# read_out.net
KiCad netlist of a schematic drawn in Altium Designer
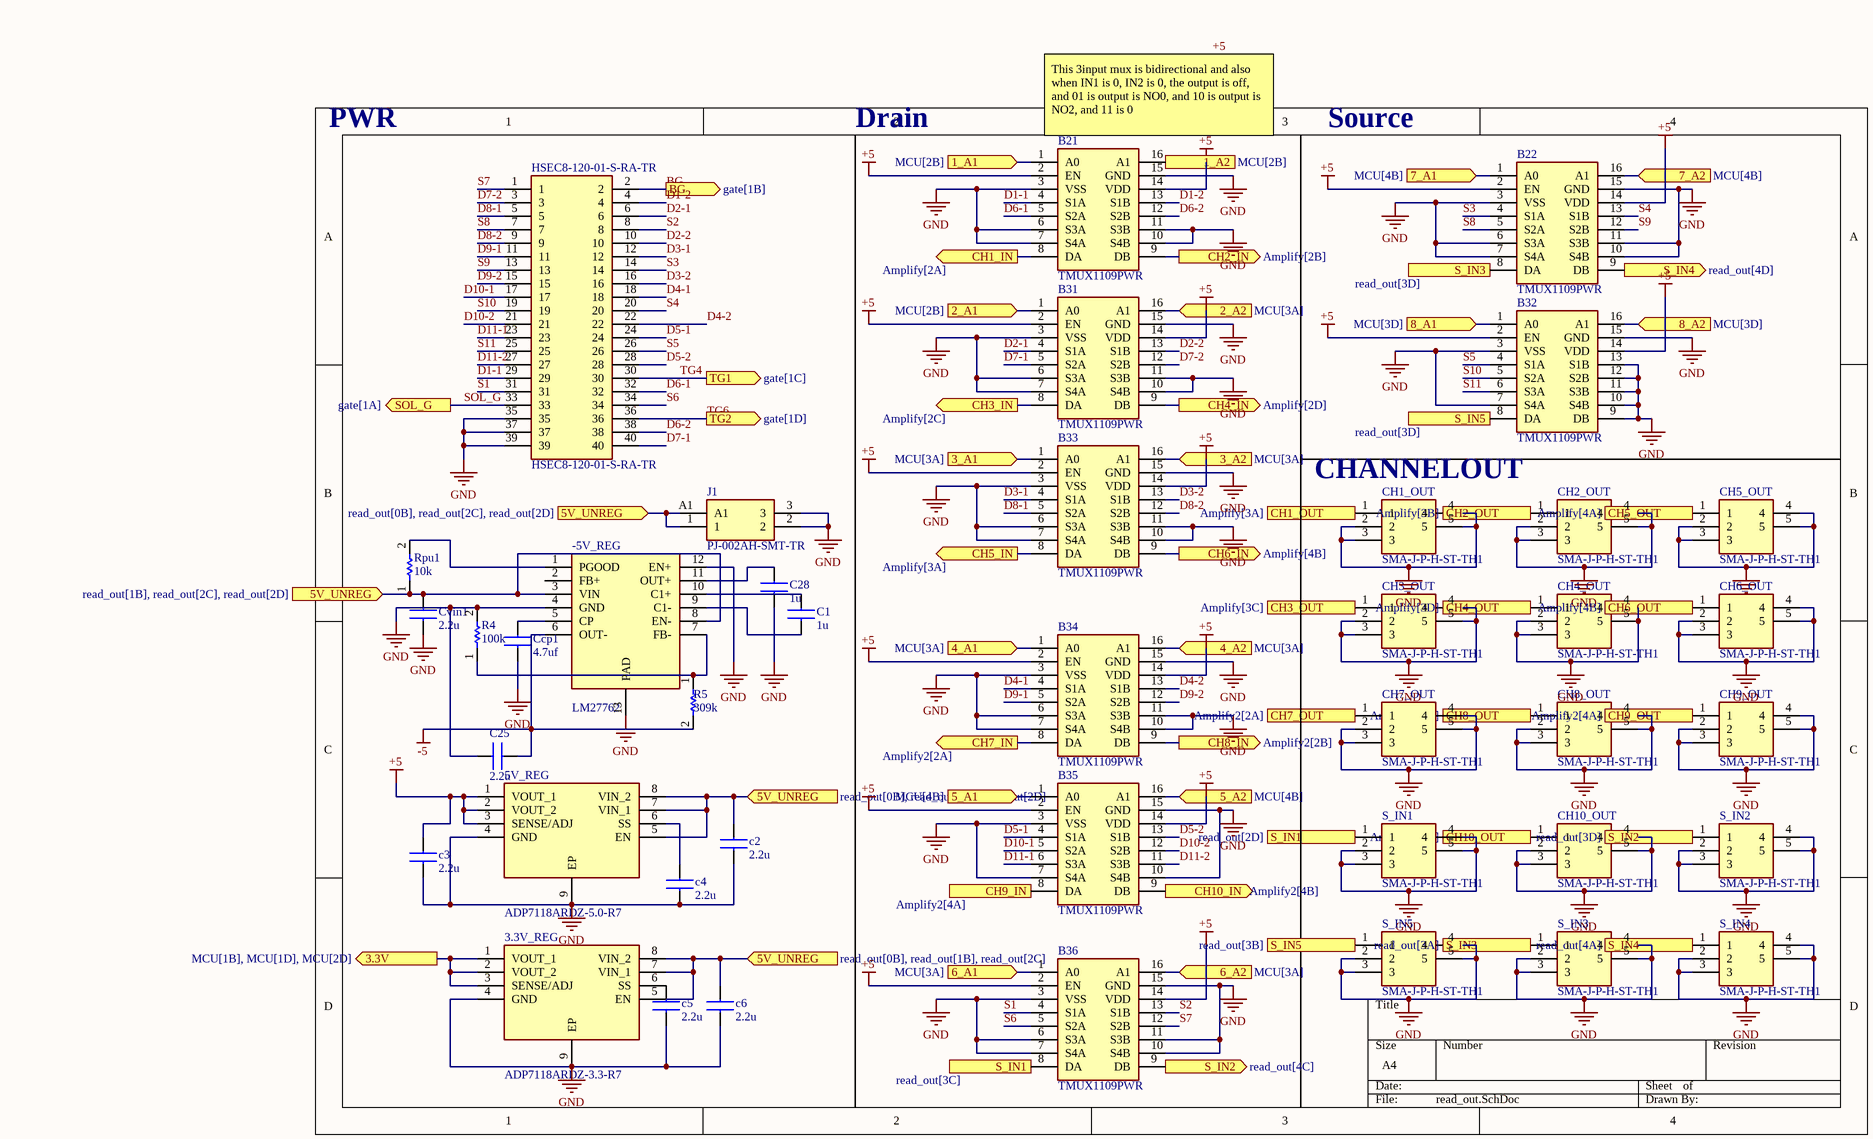
[diagram p0: read_out.SchDoc]

(export (version "E")
  (design (tool "Eeschema 10.0.6"))
  (components
    (comp (ref "-5V_REG")
      (value "LM27762")
      (footprint "LM27762")
      (libsource (lib "Schlib1") (part "LM27762"))
    )
    (comp (ref "3.3V_REG")
      (value "ADP7118ARDZ-3.3-R7")
      (footprint "ADP7118ARDZ-5.0-R7")
      (libsource (lib "Schlib1") (part "ADP7118ARDZ-5.0-R7"))
    )
    (comp (ref "5V_REG")
      (value "ADP7118ARDZ-5.0-R7")
      (footprint "ADP7118ARDZ-5.0-R7")
      (libsource (lib "Schlib1") (part "ADP7118ARDZ-5.0-R7"))
    )
    (comp (ref "B21")
      (value "TMUX1109PWR")
      (footprint "TMUX1109PWR")
      (libsource (lib "Schlib1") (part "TMUX1109PWR"))
    )
    (comp (ref "B22")
      (value "TMUX1109PWR")
      (footprint "TMUX1109PWR")
      (libsource (lib "Schlib1") (part "TMUX1109PWR"))
    )
    (comp (ref "B31")
      (value "TMUX1109PWR")
      (footprint "TMUX1109PWR")
      (libsource (lib "Schlib1") (part "TMUX1109PWR"))
    )
    (comp (ref "B32")
      (value "TMUX1109PWR")
      (footprint "TMUX1109PWR")
      (libsource (lib "Schlib1") (part "TMUX1109PWR"))
    )
    (comp (ref "B33")
      (value "TMUX1109PWR")
      (footprint "TMUX1109PWR")
      (libsource (lib "Schlib1") (part "TMUX1109PWR"))
    )
    (comp (ref "B34")
      (value "TMUX1109PWR")
      (footprint "TMUX1109PWR")
      (libsource (lib "Schlib1") (part "TMUX1109PWR"))
    )
    (comp (ref "B35")
      (value "TMUX1109PWR")
      (footprint "TMUX1109PWR")
      (libsource (lib "Schlib1") (part "TMUX1109PWR"))
    )
    (comp (ref "B36")
      (value "TMUX1109PWR")
      (footprint "TMUX1109PWR")
      (libsource (lib "Schlib1") (part "TMUX1109PWR"))
    )
    (comp (ref "C1")
      (value "1u")
      (footprint "0805X7R106KT1AT")
      (libsource (lib "Schlib1") (part "capacitor"))
    )
    (comp (ref "c2")
      (value "2.2u")
      (footprint "0805X7R106KT1AT")
      (libsource (lib "Schlib1") (part "capacitor"))
    )
    (comp (ref "c3")
      (value "2.2u")
      (footprint "0805X7R106KT1AT")
      (libsource (lib "Schlib1") (part "capacitor"))
    )
    (comp (ref "c4")
      (value "2.2u")
      (footprint "0805X7R106KT1AT")
      (libsource (lib "Schlib1") (part "capacitor"))
    )
    (comp (ref "c5")
      (value "2.2u")
      (footprint "0805X7R106KT1AT")
      (libsource (lib "Schlib1") (part "capacitor"))
    )
    (comp (ref "c6")
      (value "2.2u")
      (footprint "0805X7R106KT1AT")
      (libsource (lib "Schlib1") (part "capacitor"))
    )
    (comp (ref "C25")
      (value "2.2u")
      (footprint "0805X7R106KT1AT")
      (libsource (lib "Schlib1") (part "capacitor"))
    )
    (comp (ref "C28")
      (value "1u")
      (footprint "0805X7R106KT1AT")
      (libsource (lib "Schlib1") (part "capacitor"))
    )
    (comp (ref "Ccp1")
      (value "4.7uf")
      (footprint "0805X7R106KT1AT")
      (libsource (lib "Schlib1") (part "capacitor"))
    )
    (comp (ref "CH1_OUT")
      (value "SMA-J-P-H-ST-TH1")
      (footprint "SMAJPHSTTH1")
      (description "SAMTEC - SMA-J-P-H-ST-TH1 - RF COAXIAL, SMA JACK, 50 OHM, PCB")
      (fields (field (name "MOUSER PART NUMBER") "200-SMAJPHSTTH1"))
      (libsource (lib "Schlib1") (part "SMA-J-P-H-ST-TH1"))
    )
    (comp (ref "CH2_OUT")
      (value "SMA-J-P-H-ST-TH1")
      (footprint "SMAJPHSTTH1")
      (description "SAMTEC - SMA-J-P-H-ST-TH1 - RF COAXIAL, SMA JACK, 50 OHM, PCB")
      (fields (field (name "MOUSER PART NUMBER") "200-SMAJPHSTTH1"))
      (libsource (lib "Schlib1") (part "SMA-J-P-H-ST-TH1"))
    )
    (comp (ref "CH3_OUT")
      (value "SMA-J-P-H-ST-TH1")
      (footprint "SMAJPHSTTH1")
      (description "SAMTEC - SMA-J-P-H-ST-TH1 - RF COAXIAL, SMA JACK, 50 OHM, PCB")
      (fields (field (name "MOUSER PART NUMBER") "200-SMAJPHSTTH1"))
      (libsource (lib "Schlib1") (part "SMA-J-P-H-ST-TH1"))
    )
    (comp (ref "CH4_OUT")
      (value "SMA-J-P-H-ST-TH1")
      (footprint "SMAJPHSTTH1")
      (description "SAMTEC - SMA-J-P-H-ST-TH1 - RF COAXIAL, SMA JACK, 50 OHM, PCB")
      (fields (field (name "MOUSER PART NUMBER") "200-SMAJPHSTTH1"))
      (libsource (lib "Schlib1") (part "SMA-J-P-H-ST-TH1"))
    )
    (comp (ref "CH5_OUT")
      (value "SMA-J-P-H-ST-TH1")
      (footprint "SMAJPHSTTH1")
      (description "SAMTEC - SMA-J-P-H-ST-TH1 - RF COAXIAL, SMA JACK, 50 OHM, PCB")
      (fields (field (name "MOUSER PART NUMBER") "200-SMAJPHSTTH1"))
      (libsource (lib "Schlib1") (part "SMA-J-P-H-ST-TH1"))
    )
    (comp (ref "CH6_OUT")
      (value "SMA-J-P-H-ST-TH1")
      (footprint "SMAJPHSTTH1")
      (description "SAMTEC - SMA-J-P-H-ST-TH1 - RF COAXIAL, SMA JACK, 50 OHM, PCB")
      (fields (field (name "MOUSER PART NUMBER") "200-SMAJPHSTTH1"))
      (libsource (lib "Schlib1") (part "SMA-J-P-H-ST-TH1"))
    )
    (comp (ref "CH7_OUT")
      (value "SMA-J-P-H-ST-TH1")
      (footprint "SMAJPHSTTH1")
      (description "SAMTEC - SMA-J-P-H-ST-TH1 - RF COAXIAL, SMA JACK, 50 OHM, PCB")
      (fields (field (name "MOUSER PART NUMBER") "200-SMAJPHSTTH1"))
      (libsource (lib "Schlib1") (part "SMA-J-P-H-ST-TH1"))
    )
    (comp (ref "CH8_OUT")
      (value "SMA-J-P-H-ST-TH1")
      (footprint "SMAJPHSTTH1")
      (description "SAMTEC - SMA-J-P-H-ST-TH1 - RF COAXIAL, SMA JACK, 50 OHM, PCB")
      (fields (field (name "MOUSER PART NUMBER") "200-SMAJPHSTTH1"))
      (libsource (lib "Schlib1") (part "SMA-J-P-H-ST-TH1"))
    )
    (comp (ref "CH9_OUT")
      (value "SMA-J-P-H-ST-TH1")
      (footprint "SMAJPHSTTH1")
      (description "SAMTEC - SMA-J-P-H-ST-TH1 - RF COAXIAL, SMA JACK, 50 OHM, PCB")
      (fields (field (name "MOUSER PART NUMBER") "200-SMAJPHSTTH1"))
      (libsource (lib "Schlib1") (part "SMA-J-P-H-ST-TH1"))
    )
    (comp (ref "CH10_OUT")
      (value "SMA-J-P-H-ST-TH1")
      (footprint "SMAJPHSTTH1")
      (description "SAMTEC - SMA-J-P-H-ST-TH1 - RF COAXIAL, SMA JACK, 50 OHM, PCB")
      (fields (field (name "MOUSER PART NUMBER") "200-SMAJPHSTTH1"))
      (libsource (lib "Schlib1") (part "SMA-J-P-H-ST-TH1"))
    )
    (comp (ref "Cvin1")
      (value "2.2u")
      (footprint "0805X7R106KT1AT")
      (libsource (lib "Schlib1") (part "0805X7R106KT1AT"))
    )
    (comp (ref "HSEC8-120-01-S-RA-TR")
      (value "HSEC8-120-01-S-RA-TR")
      (footprint "SAMTEC_HSEC8-120-01-L-RA")
      (libsource (lib "Schlib1") (part "HSEC8-120-01-S-RA-TR"))
    )
    (comp (ref "J1")
      (value "PJ-002AH-SMT-TR")
      (footprint "PWRPJ")
      (libsource (lib "Schlib1") (part "Powerinput"))
    )
    (comp (ref "R4")
      (value "100k")
      (footprint "CR0805-FX-1543ELF")
      (libsource (lib "Schlib1") (part "resistor"))
    )
    (comp (ref "R5")
      (value "309k")
      (footprint "CR0805-FX-1543ELF")
      (libsource (lib "Schlib1") (part "resistor"))
    )
    (comp (ref "Rpu1")
      (value "10k")
      (footprint "CR0805-FX-1543ELF")
      (libsource (lib "Schlib1") (part "resistor"))
    )
    (comp (ref "S_IN1")
      (value "SMA-J-P-H-ST-TH1")
      (footprint "SMAJPHSTTH1")
      (description "SAMTEC - SMA-J-P-H-ST-TH1 - RF COAXIAL, SMA JACK, 50 OHM, PCB")
      (fields (field (name "MOUSER PART NUMBER") "200-SMAJPHSTTH1"))
      (libsource (lib "Schlib1") (part "SMA-J-P-H-ST-TH1"))
    )
    (comp (ref "S_IN2")
      (value "SMA-J-P-H-ST-TH1")
      (footprint "SMAJPHSTTH1")
      (description "SAMTEC - SMA-J-P-H-ST-TH1 - RF COAXIAL, SMA JACK, 50 OHM, PCB")
      (fields (field (name "MOUSER PART NUMBER") "200-SMAJPHSTTH1"))
      (libsource (lib "Schlib1") (part "SMA-J-P-H-ST-TH1"))
    )
    (comp (ref "S_IN3")
      (value "SMA-J-P-H-ST-TH1")
      (footprint "SMAJPHSTTH1")
      (description "SAMTEC - SMA-J-P-H-ST-TH1 - RF COAXIAL, SMA JACK, 50 OHM, PCB")
      (fields (field (name "MOUSER PART NUMBER") "200-SMAJPHSTTH1"))
      (libsource (lib "Schlib1") (part "SMA-J-P-H-ST-TH1"))
    )
    (comp (ref "S_IN4")
      (value "SMA-J-P-H-ST-TH1")
      (footprint "SMAJPHSTTH1")
      (description "SAMTEC - SMA-J-P-H-ST-TH1 - RF COAXIAL, SMA JACK, 50 OHM, PCB")
      (fields (field (name "MOUSER PART NUMBER") "200-SMAJPHSTTH1"))
      (libsource (lib "Schlib1") (part "SMA-J-P-H-ST-TH1"))
    )
    (comp (ref "S_IN5")
      (value "SMA-J-P-H-ST-TH1")
      (footprint "SMAJPHSTTH1")
      (description "SAMTEC - SMA-J-P-H-ST-TH1 - RF COAXIAL, SMA JACK, 50 OHM, PCB")
      (fields (field (name "MOUSER PART NUMBER") "200-SMAJPHSTTH1"))
      (libsource (lib "Schlib1") (part "SMA-J-P-H-ST-TH1"))
    )
  )
  (nets
    (net (code "1") (name "+5") (class "Default")
      (node (ref "5V_REG") (pin "1") (pinfunction "VOUT_1_1") (pintype "passive"))
      (node (ref "5V_REG") (pin "2") (pinfunction "VOUT_2_2") (pintype "passive"))
      (node (ref "5V_REG") (pin "3") (pinfunction "SENSE/ADJ_3") (pintype "passive"))
      (node (ref "B21") (pin "14") (pinfunction "VDD_14") (pintype "passive"))
      (node (ref "B21") (pin "2") (pinfunction "EN_2") (pintype "passive"))
      (node (ref "B22") (pin "14") (pinfunction "VDD_14") (pintype "passive"))
      (node (ref "B22") (pin "2") (pinfunction "EN_2") (pintype "passive"))
      (node (ref "B31") (pin "14") (pinfunction "VDD_14") (pintype "passive"))
      (node (ref "B31") (pin "2") (pinfunction "EN_2") (pintype "passive"))
      (node (ref "B32") (pin "14") (pinfunction "VDD_14") (pintype "passive"))
      (node (ref "B32") (pin "2") (pinfunction "EN_2") (pintype "passive"))
      (node (ref "B33") (pin "14") (pinfunction "VDD_14") (pintype "passive"))
      (node (ref "B33") (pin "2") (pinfunction "EN_2") (pintype "passive"))
      (node (ref "B34") (pin "14") (pinfunction "VDD_14") (pintype "passive"))
      (node (ref "B34") (pin "2") (pinfunction "EN_2") (pintype "passive"))
      (node (ref "B35") (pin "14") (pinfunction "VDD_14") (pintype "passive"))
      (node (ref "B35") (pin "2") (pinfunction "EN_2") (pintype "passive"))
      (node (ref "B36") (pin "14") (pinfunction "VDD_14") (pintype "passive"))
      (node (ref "B36") (pin "2") (pinfunction "EN_2") (pintype "passive"))
      (node (ref "c3") (pin "2") (pinfunction "2_2") (pintype "passive"))
    )
    (net (code "2") (name "-5") (class "Default")
      (node (ref "-5V_REG") (pin "6") (pinfunction "OUT-_6") (pintype "power_in"))
      (node (ref "C25") (pin "1") (pinfunction "1_1") (pintype "passive"))
      (node (ref "R5") (pin "2") (pinfunction "2_2") (pintype "passive"))
    )
    (net (code "3") (name "/1_A1") (class "Default")
      (node (ref "B21") (pin "1") (pinfunction "A0_1") (pintype "passive"))
    )
    (net (code "4") (name "/1_A2") (class "Default")
      (node (ref "B21") (pin "16") (pinfunction "A1_16") (pintype "passive"))
    )
    (net (code "5") (name "/2_A1") (class "Default")
      (node (ref "B31") (pin "1") (pinfunction "A0_1") (pintype "passive"))
    )
    (net (code "6") (name "/2_A2") (class "Default")
      (node (ref "B31") (pin "16") (pinfunction "A1_16") (pintype "passive"))
    )
    (net (code "7") (name "/3.3V") (class "Default")
      (node (ref "3.3V_REG") (pin "1") (pinfunction "VOUT_1_1") (pintype "passive"))
      (node (ref "3.3V_REG") (pin "2") (pinfunction "VOUT_2_2") (pintype "passive"))
      (node (ref "3.3V_REG") (pin "3") (pinfunction "SENSE/ADJ_3") (pintype "passive"))
    )
    (net (code "8") (name "/3_A1") (class "Default")
      (node (ref "B33") (pin "1") (pinfunction "A0_1") (pintype "passive"))
    )
    (net (code "9") (name "/3_A2") (class "Default")
      (node (ref "B33") (pin "16") (pinfunction "A1_16") (pintype "passive"))
    )
    (net (code "10") (name "/4_A1") (class "Default")
      (node (ref "B34") (pin "1") (pinfunction "A0_1") (pintype "passive"))
    )
    (net (code "11") (name "/4_A2") (class "Default")
      (node (ref "B34") (pin "16") (pinfunction "A1_16") (pintype "passive"))
    )
    (net (code "12") (name "/5V_UNREG") (class "Default")
      (node (ref "-5V_REG") (pin "3") (pinfunction "VIN_3") (pintype "power_in"))
      (node (ref "-5V_REG") (pin "8") (pinfunction "EN-_8") (pintype "passive"))
      (node (ref "3.3V_REG") (pin "5") (pinfunction "EN_5") (pintype "passive"))
      (node (ref "3.3V_REG") (pin "7") (pinfunction "VIN_1_7") (pintype "passive"))
      (node (ref "3.3V_REG") (pin "8") (pinfunction "VIN_2_8") (pintype "passive"))
      (node (ref "5V_REG") (pin "5") (pinfunction "EN_5") (pintype "passive"))
      (node (ref "5V_REG") (pin "7") (pinfunction "VIN_1_7") (pintype "passive"))
      (node (ref "5V_REG") (pin "8") (pinfunction "VIN_2_8") (pintype "passive"))
      (node (ref "Cvin1") (pin "2") (pinfunction "2_2") (pintype "passive"))
      (node (ref "J1") (pin "1") (pinfunction "1_1") (pintype "passive"))
      (node (ref "J1") (pin "A1") (pinfunction "A1_A1") (pintype "passive"))
      (node (ref "Rpu1") (pin "1") (pinfunction "1_1") (pintype "passive"))
      (node (ref "c2") (pin "2") (pinfunction "2_2") (pintype "passive"))
      (node (ref "c6") (pin "2") (pinfunction "2_2") (pintype "passive"))
    )
    (net (code "13") (name "/5_A1") (class "Default")
      (node (ref "B35") (pin "1") (pinfunction "A0_1") (pintype "passive"))
    )
    (net (code "14") (name "/5_A2") (class "Default")
      (node (ref "B35") (pin "16") (pinfunction "A1_16") (pintype "passive"))
    )
    (net (code "15") (name "/6_A1") (class "Default")
      (node (ref "B36") (pin "1") (pinfunction "A0_1") (pintype "passive"))
    )
    (net (code "16") (name "/6_A2") (class "Default")
      (node (ref "B36") (pin "16") (pinfunction "A1_16") (pintype "passive"))
    )
    (net (code "17") (name "/7_A1") (class "Default")
      (node (ref "B22") (pin "1") (pinfunction "A0_1") (pintype "passive"))
    )
    (net (code "18") (name "/7_A2") (class "Default")
      (node (ref "B22") (pin "16") (pinfunction "A1_16") (pintype "passive"))
    )
    (net (code "19") (name "/8_A1") (class "Default")
      (node (ref "B32") (pin "1") (pinfunction "A0_1") (pintype "passive"))
    )
    (net (code "20") (name "/8_A2") (class "Default")
      (node (ref "B32") (pin "16") (pinfunction "A1_16") (pintype "passive"))
    )
    (net (code "21") (name "/BG") (class "Default")
      (node (ref "HSEC8-120-01-S-RA-TR") (pin "2") (pinfunction "2_2") (pintype "passive"))
    )
    (net (code "22") (name "/CH1_IN") (class "Default")
      (node (ref "B21") (pin "8") (pinfunction "DA_8") (pintype "passive"))
    )
    (net (code "23") (name "/CH1_OUT") (class "Default")
      (node (ref "CH1_OUT") (pin "1") (pinfunction "1_1") (pintype "passive"))
    )
    (net (code "24") (name "/CH2_IN") (class "Default")
      (node (ref "B21") (pin "9") (pinfunction "DB_9") (pintype "passive"))
    )
    (net (code "25") (name "/CH2_OUT") (class "Default")
      (node (ref "CH2_OUT") (pin "1") (pinfunction "1_1") (pintype "passive"))
    )
    (net (code "26") (name "/CH3_IN") (class "Default")
      (node (ref "B31") (pin "8") (pinfunction "DA_8") (pintype "passive"))
    )
    (net (code "27") (name "/CH3_OUT") (class "Default")
      (node (ref "CH3_OUT") (pin "1") (pinfunction "1_1") (pintype "passive"))
    )
    (net (code "28") (name "/CH4_IN") (class "Default")
      (node (ref "B31") (pin "9") (pinfunction "DB_9") (pintype "passive"))
    )
    (net (code "29") (name "/CH4_OUT") (class "Default")
      (node (ref "CH4_OUT") (pin "1") (pinfunction "1_1") (pintype "passive"))
    )
    (net (code "30") (name "/CH5_IN") (class "Default")
      (node (ref "B33") (pin "8") (pinfunction "DA_8") (pintype "passive"))
    )
    (net (code "31") (name "/CH5_OUT") (class "Default")
      (node (ref "CH5_OUT") (pin "1") (pinfunction "1_1") (pintype "passive"))
    )
    (net (code "32") (name "/CH6_IN") (class "Default")
      (node (ref "B33") (pin "9") (pinfunction "DB_9") (pintype "passive"))
    )
    (net (code "33") (name "/CH6_OUT") (class "Default")
      (node (ref "CH6_OUT") (pin "1") (pinfunction "1_1") (pintype "passive"))
    )
    (net (code "34") (name "/CH7_IN") (class "Default")
      (node (ref "B34") (pin "8") (pinfunction "DA_8") (pintype "passive"))
    )
    (net (code "35") (name "/CH7_OUT") (class "Default")
      (node (ref "CH7_OUT") (pin "1") (pinfunction "1_1") (pintype "passive"))
    )
    (net (code "36") (name "/CH8_IN") (class "Default")
      (node (ref "B34") (pin "9") (pinfunction "DB_9") (pintype "passive"))
    )
    (net (code "37") (name "/CH8_OUT") (class "Default")
      (node (ref "CH8_OUT") (pin "1") (pinfunction "1_1") (pintype "passive"))
    )
    (net (code "38") (name "/CH9_IN") (class "Default")
      (node (ref "B35") (pin "8") (pinfunction "DA_8") (pintype "passive"))
    )
    (net (code "39") (name "/CH9_OUT") (class "Default")
      (node (ref "CH9_OUT") (pin "1") (pinfunction "1_1") (pintype "passive"))
    )
    (net (code "40") (name "/CH10_IN") (class "Default")
      (node (ref "B35") (pin "9") (pinfunction "DB_9") (pintype "passive"))
    )
    (net (code "41") (name "/CH10_OUT") (class "Default")
      (node (ref "CH10_OUT") (pin "1") (pinfunction "1_1") (pintype "passive"))
    )
    (net (code "42") (name "/D1-1") (class "Default")
      (node (ref "B21") (pin "4") (pinfunction "S1A_4") (pintype "passive"))
      (node (ref "HSEC8-120-01-S-RA-TR") (pin "29") (pinfunction "29_29") (pintype "passive"))
    )
    (net (code "43") (name "/D1-2") (class "Default")
      (node (ref "B21") (pin "13") (pinfunction "S1B_13") (pintype "passive"))
      (node (ref "HSEC8-120-01-S-RA-TR") (pin "4") (pinfunction "4_4") (pintype "passive"))
    )
    (net (code "44") (name "/D2-1") (class "Default")
      (node (ref "B31") (pin "4") (pinfunction "S1A_4") (pintype "passive"))
      (node (ref "HSEC8-120-01-S-RA-TR") (pin "6") (pinfunction "6_6") (pintype "passive"))
    )
    (net (code "45") (name "/D2-2") (class "Default")
      (node (ref "B31") (pin "13") (pinfunction "S1B_13") (pintype "passive"))
      (node (ref "HSEC8-120-01-S-RA-TR") (pin "10") (pinfunction "10_10") (pintype "passive"))
    )
    (net (code "46") (name "/D3-1") (class "Default")
      (node (ref "B33") (pin "4") (pinfunction "S1A_4") (pintype "passive"))
      (node (ref "HSEC8-120-01-S-RA-TR") (pin "12") (pinfunction "12_12") (pintype "passive"))
    )
    (net (code "47") (name "/D3-2") (class "Default")
      (node (ref "B33") (pin "13") (pinfunction "S1B_13") (pintype "passive"))
      (node (ref "HSEC8-120-01-S-RA-TR") (pin "16") (pinfunction "16_16") (pintype "passive"))
    )
    (net (code "48") (name "/D4-1") (class "Default")
      (node (ref "B34") (pin "4") (pinfunction "S1A_4") (pintype "passive"))
      (node (ref "HSEC8-120-01-S-RA-TR") (pin "18") (pinfunction "18_18") (pintype "passive"))
    )
    (net (code "49") (name "/D4-2") (class "Default")
      (node (ref "B34") (pin "13") (pinfunction "S1B_13") (pintype "passive"))
      (node (ref "HSEC8-120-01-S-RA-TR") (pin "22") (pinfunction "22_22") (pintype "passive"))
    )
    (net (code "50") (name "/D5-1") (class "Default")
      (node (ref "B35") (pin "4") (pinfunction "S1A_4") (pintype "passive"))
      (node (ref "HSEC8-120-01-S-RA-TR") (pin "24") (pinfunction "24_24") (pintype "passive"))
    )
    (net (code "51") (name "/D5-2") (class "Default")
      (node (ref "B35") (pin "13") (pinfunction "S1B_13") (pintype "passive"))
      (node (ref "HSEC8-120-01-S-RA-TR") (pin "28") (pinfunction "28_28") (pintype "passive"))
    )
    (net (code "52") (name "/D6-1") (class "Default")
      (node (ref "B21") (pin "5") (pinfunction "S2A_5") (pintype "passive"))
      (node (ref "HSEC8-120-01-S-RA-TR") (pin "32") (pinfunction "32_32") (pintype "passive"))
    )
    (net (code "53") (name "/D6-2") (class "Default")
      (node (ref "B21") (pin "12") (pinfunction "S2B_12") (pintype "passive"))
      (node (ref "HSEC8-120-01-S-RA-TR") (pin "38") (pinfunction "38_38") (pintype "passive"))
    )
    (net (code "54") (name "/D7-1") (class "Default")
      (node (ref "B31") (pin "5") (pinfunction "S2A_5") (pintype "passive"))
      (node (ref "HSEC8-120-01-S-RA-TR") (pin "40") (pinfunction "40_40") (pintype "passive"))
    )
    (net (code "55") (name "/D7-2") (class "Default")
      (node (ref "B31") (pin "12") (pinfunction "S2B_12") (pintype "passive"))
      (node (ref "HSEC8-120-01-S-RA-TR") (pin "3") (pinfunction "3_3") (pintype "passive"))
    )
    (net (code "56") (name "/D8-1") (class "Default")
      (node (ref "B33") (pin "5") (pinfunction "S2A_5") (pintype "passive"))
      (node (ref "HSEC8-120-01-S-RA-TR") (pin "5") (pinfunction "5_5") (pintype "passive"))
    )
    (net (code "57") (name "/D8-2") (class "Default")
      (node (ref "B33") (pin "12") (pinfunction "S2B_12") (pintype "passive"))
      (node (ref "HSEC8-120-01-S-RA-TR") (pin "9") (pinfunction "9_9") (pintype "passive"))
    )
    (net (code "58") (name "/D9-1") (class "Default")
      (node (ref "B34") (pin "5") (pinfunction "S2A_5") (pintype "passive"))
      (node (ref "HSEC8-120-01-S-RA-TR") (pin "11") (pinfunction "11_11") (pintype "passive"))
    )
    (net (code "59") (name "/D9-2") (class "Default")
      (node (ref "B34") (pin "12") (pinfunction "S2B_12") (pintype "passive"))
      (node (ref "HSEC8-120-01-S-RA-TR") (pin "15") (pinfunction "15_15") (pintype "passive"))
    )
    (net (code "60") (name "/D10-1") (class "Default")
      (node (ref "B35") (pin "5") (pinfunction "S2A_5") (pintype "passive"))
      (node (ref "HSEC8-120-01-S-RA-TR") (pin "17") (pinfunction "17_17") (pintype "passive"))
    )
    (net (code "61") (name "/D10-2") (class "Default")
      (node (ref "B35") (pin "12") (pinfunction "S2B_12") (pintype "passive"))
      (node (ref "HSEC8-120-01-S-RA-TR") (pin "21") (pinfunction "21_21") (pintype "passive"))
    )
    (net (code "62") (name "/D11-1") (class "Default")
      (node (ref "B35") (pin "6") (pinfunction "S3A_6") (pintype "passive"))
      (node (ref "HSEC8-120-01-S-RA-TR") (pin "23") (pinfunction "23_23") (pintype "passive"))
    )
    (net (code "63") (name "/D11-2") (class "Default")
      (node (ref "B35") (pin "11") (pinfunction "S3B_11") (pintype "passive"))
      (node (ref "HSEC8-120-01-S-RA-TR") (pin "27") (pinfunction "27_27") (pintype "passive"))
    )
    (net (code "64") (name "/S1") (class "Default")
      (node (ref "B36") (pin "4") (pinfunction "S1A_4") (pintype "passive"))
      (node (ref "HSEC8-120-01-S-RA-TR") (pin "31") (pinfunction "31_31") (pintype "passive"))
    )
    (net (code "65") (name "/S2") (class "Default")
      (node (ref "B36") (pin "13") (pinfunction "S1B_13") (pintype "passive"))
      (node (ref "HSEC8-120-01-S-RA-TR") (pin "8") (pinfunction "8_8") (pintype "passive"))
    )
    (net (code "66") (name "/S3") (class "Default")
      (node (ref "B22") (pin "4") (pinfunction "S1A_4") (pintype "passive"))
      (node (ref "HSEC8-120-01-S-RA-TR") (pin "14") (pinfunction "14_14") (pintype "passive"))
    )
    (net (code "67") (name "/S4") (class "Default")
      (node (ref "B22") (pin "13") (pinfunction "S1B_13") (pintype "passive"))
      (node (ref "HSEC8-120-01-S-RA-TR") (pin "20") (pinfunction "20_20") (pintype "passive"))
    )
    (net (code "68") (name "/S5") (class "Default")
      (node (ref "B32") (pin "4") (pinfunction "S1A_4") (pintype "passive"))
      (node (ref "HSEC8-120-01-S-RA-TR") (pin "26") (pinfunction "26_26") (pintype "passive"))
    )
    (net (code "69") (name "/S6") (class "Default")
      (node (ref "B36") (pin "5") (pinfunction "S2A_5") (pintype "passive"))
      (node (ref "HSEC8-120-01-S-RA-TR") (pin "34") (pinfunction "34_34") (pintype "passive"))
    )
    (net (code "70") (name "/S7") (class "Default")
      (node (ref "B36") (pin "12") (pinfunction "S2B_12") (pintype "passive"))
      (node (ref "HSEC8-120-01-S-RA-TR") (pin "1") (pinfunction "1_1") (pintype "passive"))
    )
    (net (code "71") (name "/S8") (class "Default")
      (node (ref "B22") (pin "5") (pinfunction "S2A_5") (pintype "passive"))
      (node (ref "HSEC8-120-01-S-RA-TR") (pin "7") (pinfunction "7_7") (pintype "passive"))
    )
    (net (code "72") (name "/S9") (class "Default")
      (node (ref "B22") (pin "12") (pinfunction "S2B_12") (pintype "passive"))
      (node (ref "HSEC8-120-01-S-RA-TR") (pin "13") (pinfunction "13_13") (pintype "passive"))
    )
    (net (code "73") (name "/S10") (class "Default")
      (node (ref "B32") (pin "5") (pinfunction "S2A_5") (pintype "passive"))
      (node (ref "HSEC8-120-01-S-RA-TR") (pin "19") (pinfunction "19_19") (pintype "passive"))
    )
    (net (code "74") (name "/S11") (class "Default")
      (node (ref "B32") (pin "6") (pinfunction "S3A_6") (pintype "passive"))
      (node (ref "HSEC8-120-01-S-RA-TR") (pin "25") (pinfunction "25_25") (pintype "passive"))
    )
    (net (code "75") (name "/SOL_G") (class "Default")
      (node (ref "HSEC8-120-01-S-RA-TR") (pin "33") (pinfunction "33_33") (pintype "passive"))
    )
    (net (code "76") (name "/S_IN1") (class "Default")
      (node (ref "B36") (pin "8") (pinfunction "DA_8") (pintype "passive"))
      (node (ref "S_IN1") (pin "1") (pinfunction "1_1") (pintype "passive"))
    )
    (net (code "77") (name "/S_IN2") (class "Default")
      (node (ref "B36") (pin "9") (pinfunction "DB_9") (pintype "passive"))
      (node (ref "S_IN2") (pin "1") (pinfunction "1_1") (pintype "passive"))
    )
    (net (code "78") (name "/S_IN3") (class "Default")
      (node (ref "B22") (pin "8") (pinfunction "DA_8") (pintype "passive"))
      (node (ref "S_IN3") (pin "1") (pinfunction "1_1") (pintype "passive"))
    )
    (net (code "79") (name "/S_IN4") (class "Default")
      (node (ref "B22") (pin "9") (pinfunction "DB_9") (pintype "passive"))
      (node (ref "S_IN4") (pin "1") (pinfunction "1_1") (pintype "passive"))
    )
    (net (code "80") (name "/S_IN5") (class "Default")
      (node (ref "B32") (pin "8") (pinfunction "DA_8") (pintype "passive"))
      (node (ref "S_IN5") (pin "1") (pinfunction "1_1") (pintype "passive"))
    )
    (net (code "81") (name "/TG4") (class "Default")
      (node (ref "HSEC8-120-01-S-RA-TR") (pin "30") (pinfunction "30_30") (pintype "passive"))
    )
    (net (code "82") (name "/TG6") (class "Default")
      (node (ref "HSEC8-120-01-S-RA-TR") (pin "36") (pinfunction "36_36") (pintype "passive"))
    )
    (net (code "83") (name "GND") (class "Default")
      (node (ref "-5V_REG") (pin "12") (pinfunction "EN+_12") (pintype "passive"))
      (node (ref "-5V_REG") (pin "13") (pinfunction "PAD_13") (pintype "passive"))
      (node (ref "-5V_REG") (pin "4") (pinfunction "GND_4") (pintype "passive"))
      (node (ref "3.3V_REG") (pin "4") (pinfunction "GND_4") (pintype "passive"))
      (node (ref "3.3V_REG") (pin "9") (pinfunction "EP_9") (pintype "passive"))
      (node (ref "5V_REG") (pin "4") (pinfunction "GND_4") (pintype "passive"))
      (node (ref "5V_REG") (pin "9") (pinfunction "EP_9") (pintype "passive"))
      (node (ref "B21") (pin "10") (pinfunction "S4B_10") (pintype "passive"))
      (node (ref "B21") (pin "11") (pinfunction "S3B_11") (pintype "passive"))
      (node (ref "B21") (pin "15") (pinfunction "GND_15") (pintype "passive"))
      (node (ref "B21") (pin "3") (pinfunction "VSS_3") (pintype "passive"))
      (node (ref "B21") (pin "6") (pinfunction "S3A_6") (pintype "passive"))
      (node (ref "B21") (pin "7") (pinfunction "S4A_7") (pintype "passive"))
      (node (ref "B22") (pin "10") (pinfunction "S4B_10") (pintype "passive"))
      (node (ref "B22") (pin "11") (pinfunction "S3B_11") (pintype "passive"))
      (node (ref "B22") (pin "15") (pinfunction "GND_15") (pintype "passive"))
      (node (ref "B22") (pin "3") (pinfunction "VSS_3") (pintype "passive"))
      (node (ref "B22") (pin "6") (pinfunction "S3A_6") (pintype "passive"))
      (node (ref "B22") (pin "7") (pinfunction "S4A_7") (pintype "passive"))
      (node (ref "B31") (pin "10") (pinfunction "S4B_10") (pintype "passive"))
      (node (ref "B31") (pin "11") (pinfunction "S3B_11") (pintype "passive"))
      (node (ref "B31") (pin "15") (pinfunction "GND_15") (pintype "passive"))
      (node (ref "B31") (pin "3") (pinfunction "VSS_3") (pintype "passive"))
      (node (ref "B31") (pin "6") (pinfunction "S3A_6") (pintype "passive"))
      (node (ref "B31") (pin "7") (pinfunction "S4A_7") (pintype "passive"))
      (node (ref "B32") (pin "10") (pinfunction "S4B_10") (pintype "passive"))
      (node (ref "B32") (pin "11") (pinfunction "S3B_11") (pintype "passive"))
      (node (ref "B32") (pin "12") (pinfunction "S2B_12") (pintype "passive"))
      (node (ref "B32") (pin "13") (pinfunction "S1B_13") (pintype "passive"))
      (node (ref "B32") (pin "15") (pinfunction "GND_15") (pintype "passive"))
      (node (ref "B32") (pin "3") (pinfunction "VSS_3") (pintype "passive"))
      (node (ref "B32") (pin "7") (pinfunction "S4A_7") (pintype "passive"))
      (node (ref "B32") (pin "9") (pinfunction "DB_9") (pintype "passive"))
      (node (ref "B33") (pin "10") (pinfunction "S4B_10") (pintype "passive"))
      (node (ref "B33") (pin "11") (pinfunction "S3B_11") (pintype "passive"))
      (node (ref "B33") (pin "15") (pinfunction "GND_15") (pintype "passive"))
      (node (ref "B33") (pin "3") (pinfunction "VSS_3") (pintype "passive"))
      (node (ref "B33") (pin "6") (pinfunction "S3A_6") (pintype "passive"))
      (node (ref "B33") (pin "7") (pinfunction "S4A_7") (pintype "passive"))
      (node (ref "B34") (pin "10") (pinfunction "S4B_10") (pintype "passive"))
      (node (ref "B34") (pin "11") (pinfunction "S3B_11") (pintype "passive"))
      (node (ref "B34") (pin "15") (pinfunction "GND_15") (pintype "passive"))
      (node (ref "B34") (pin "3") (pinfunction "VSS_3") (pintype "passive"))
      (node (ref "B34") (pin "6") (pinfunction "S3A_6") (pintype "passive"))
      (node (ref "B34") (pin "7") (pinfunction "S4A_7") (pintype "passive"))
      (node (ref "B35") (pin "10") (pinfunction "S4B_10") (pintype "passive"))
      (node (ref "B35") (pin "15") (pinfunction "GND_15") (pintype "passive"))
      (node (ref "B35") (pin "3") (pinfunction "VSS_3") (pintype "passive"))
      (node (ref "B35") (pin "7") (pinfunction "S4A_7") (pintype "passive"))
      (node (ref "B36") (pin "10") (pinfunction "S4B_10") (pintype "passive"))
      (node (ref "B36") (pin "11") (pinfunction "S3B_11") (pintype "passive"))
      (node (ref "B36") (pin "15") (pinfunction "GND_15") (pintype "passive"))
      (node (ref "B36") (pin "3") (pinfunction "VSS_3") (pintype "passive"))
      (node (ref "B36") (pin "6") (pinfunction "S3A_6") (pintype "passive"))
      (node (ref "B36") (pin "7") (pinfunction "S4A_7") (pintype "passive"))
      (node (ref "C25") (pin "2") (pinfunction "2_2") (pintype "passive"))
      (node (ref "C28") (pin "1") (pinfunction "1_1") (pintype "passive"))
      (node (ref "CH10_OUT") (pin "2") (pinfunction "2_2") (pintype "passive"))
      (node (ref "CH10_OUT") (pin "3") (pinfunction "3_3") (pintype "passive"))
      (node (ref "CH10_OUT") (pin "4") (pinfunction "4_4") (pintype "passive"))
      (node (ref "CH10_OUT") (pin "5") (pinfunction "5_5") (pintype "passive"))
      (node (ref "CH1_OUT") (pin "2") (pinfunction "2_2") (pintype "passive"))
      (node (ref "CH1_OUT") (pin "3") (pinfunction "3_3") (pintype "passive"))
      (node (ref "CH1_OUT") (pin "4") (pinfunction "4_4") (pintype "passive"))
      (node (ref "CH1_OUT") (pin "5") (pinfunction "5_5") (pintype "passive"))
      (node (ref "CH2_OUT") (pin "2") (pinfunction "2_2") (pintype "passive"))
      (node (ref "CH2_OUT") (pin "3") (pinfunction "3_3") (pintype "passive"))
      (node (ref "CH2_OUT") (pin "4") (pinfunction "4_4") (pintype "passive"))
      (node (ref "CH2_OUT") (pin "5") (pinfunction "5_5") (pintype "passive"))
      (node (ref "CH3_OUT") (pin "2") (pinfunction "2_2") (pintype "passive"))
      (node (ref "CH3_OUT") (pin "3") (pinfunction "3_3") (pintype "passive"))
      (node (ref "CH3_OUT") (pin "4") (pinfunction "4_4") (pintype "passive"))
      (node (ref "CH3_OUT") (pin "5") (pinfunction "5_5") (pintype "passive"))
      (node (ref "CH4_OUT") (pin "2") (pinfunction "2_2") (pintype "passive"))
      (node (ref "CH4_OUT") (pin "3") (pinfunction "3_3") (pintype "passive"))
      (node (ref "CH4_OUT") (pin "4") (pinfunction "4_4") (pintype "passive"))
      (node (ref "CH4_OUT") (pin "5") (pinfunction "5_5") (pintype "passive"))
      (node (ref "CH5_OUT") (pin "2") (pinfunction "2_2") (pintype "passive"))
      (node (ref "CH5_OUT") (pin "3") (pinfunction "3_3") (pintype "passive"))
      (node (ref "CH5_OUT") (pin "4") (pinfunction "4_4") (pintype "passive"))
      (node (ref "CH5_OUT") (pin "5") (pinfunction "5_5") (pintype "passive"))
      (node (ref "CH6_OUT") (pin "2") (pinfunction "2_2") (pintype "passive"))
      (node (ref "CH6_OUT") (pin "3") (pinfunction "3_3") (pintype "passive"))
      (node (ref "CH6_OUT") (pin "4") (pinfunction "4_4") (pintype "passive"))
      (node (ref "CH6_OUT") (pin "5") (pinfunction "5_5") (pintype "passive"))
      (node (ref "CH7_OUT") (pin "2") (pinfunction "2_2") (pintype "passive"))
      (node (ref "CH7_OUT") (pin "3") (pinfunction "3_3") (pintype "passive"))
      (node (ref "CH7_OUT") (pin "4") (pinfunction "4_4") (pintype "passive"))
      (node (ref "CH7_OUT") (pin "5") (pinfunction "5_5") (pintype "passive"))
      (node (ref "CH8_OUT") (pin "2") (pinfunction "2_2") (pintype "passive"))
      (node (ref "CH8_OUT") (pin "3") (pinfunction "3_3") (pintype "passive"))
      (node (ref "CH8_OUT") (pin "4") (pinfunction "4_4") (pintype "passive"))
      (node (ref "CH8_OUT") (pin "5") (pinfunction "5_5") (pintype "passive"))
      (node (ref "CH9_OUT") (pin "2") (pinfunction "2_2") (pintype "passive"))
      (node (ref "CH9_OUT") (pin "3") (pinfunction "3_3") (pintype "passive"))
      (node (ref "CH9_OUT") (pin "4") (pinfunction "4_4") (pintype "passive"))
      (node (ref "CH9_OUT") (pin "5") (pinfunction "5_5") (pintype "passive"))
      (node (ref "Ccp1") (pin "1") (pinfunction "1_1") (pintype "passive"))
      (node (ref "Cvin1") (pin "1") (pinfunction "1_1") (pintype "passive"))
      (node (ref "HSEC8-120-01-S-RA-TR") (pin "35") (pinfunction "35_35") (pintype "passive"))
      (node (ref "HSEC8-120-01-S-RA-TR") (pin "37") (pinfunction "37_37") (pintype "passive"))
      (node (ref "HSEC8-120-01-S-RA-TR") (pin "39") (pinfunction "39_39") (pintype "passive"))
      (node (ref "J1") (pin "2") (pinfunction "2_2") (pintype "passive"))
      (node (ref "J1") (pin "3") (pinfunction "3_3") (pintype "passive"))
      (node (ref "R4") (pin "2") (pinfunction "2_2") (pintype "passive"))
      (node (ref "S_IN1") (pin "2") (pinfunction "2_2") (pintype "passive"))
      (node (ref "S_IN1") (pin "3") (pinfunction "3_3") (pintype "passive"))
      (node (ref "S_IN1") (pin "4") (pinfunction "4_4") (pintype "passive"))
      (node (ref "S_IN1") (pin "5") (pinfunction "5_5") (pintype "passive"))
      (node (ref "S_IN2") (pin "2") (pinfunction "2_2") (pintype "passive"))
      (node (ref "S_IN2") (pin "3") (pinfunction "3_3") (pintype "passive"))
      (node (ref "S_IN2") (pin "4") (pinfunction "4_4") (pintype "passive"))
      (node (ref "S_IN2") (pin "5") (pinfunction "5_5") (pintype "passive"))
      (node (ref "S_IN3") (pin "2") (pinfunction "2_2") (pintype "passive"))
      (node (ref "S_IN3") (pin "3") (pinfunction "3_3") (pintype "passive"))
      (node (ref "S_IN3") (pin "4") (pinfunction "4_4") (pintype "passive"))
      (node (ref "S_IN3") (pin "5") (pinfunction "5_5") (pintype "passive"))
      (node (ref "S_IN4") (pin "2") (pinfunction "2_2") (pintype "passive"))
      (node (ref "S_IN4") (pin "3") (pinfunction "3_3") (pintype "passive"))
      (node (ref "S_IN4") (pin "4") (pinfunction "4_4") (pintype "passive"))
      (node (ref "S_IN4") (pin "5") (pinfunction "5_5") (pintype "passive"))
      (node (ref "S_IN5") (pin "2") (pinfunction "2_2") (pintype "passive"))
      (node (ref "S_IN5") (pin "3") (pinfunction "3_3") (pintype "passive"))
      (node (ref "S_IN5") (pin "4") (pinfunction "4_4") (pintype "passive"))
      (node (ref "S_IN5") (pin "5") (pinfunction "5_5") (pintype "passive"))
      (node (ref "c2") (pin "1") (pinfunction "1_1") (pintype "passive"))
      (node (ref "c3") (pin "1") (pinfunction "1_1") (pintype "passive"))
      (node (ref "c4") (pin "1") (pinfunction "1_1") (pintype "passive"))
      (node (ref "c5") (pin "1") (pinfunction "1_1") (pintype "passive"))
      (node (ref "c6") (pin "1") (pinfunction "1_1") (pintype "passive"))
    )
    (net (code "84") (name "Net-(-5V_REG-C1+)") (class "Default")
      (node (ref "-5V_REG") (pin "10") (pinfunction "C1+_10") (pintype "power_in"))
      (node (ref "C1") (pin "2") (pinfunction "2_2") (pintype "passive"))
    )
    (net (code "85") (name "Net-(-5V_REG-C1-)") (class "Default")
      (node (ref "-5V_REG") (pin "9") (pinfunction "C1-_9") (pintype "power_in"))
      (node (ref "C1") (pin "1") (pinfunction "1_1") (pintype "passive"))
    )
    (net (code "86") (name "Net-(-5V_REG-CP)") (class "Default")
      (node (ref "-5V_REG") (pin "5") (pinfunction "CP_5") (pintype "power_in"))
      (node (ref "Ccp1") (pin "2") (pinfunction "2_2") (pintype "passive"))
    )
    (net (code "87") (name "Net-(-5V_REG-FB-)") (class "Default")
      (node (ref "-5V_REG") (pin "7") (pinfunction "FB-_7") (pintype "power_in"))
      (node (ref "R4") (pin "1") (pinfunction "1_1") (pintype "passive"))
      (node (ref "R5") (pin "1") (pinfunction "1_1") (pintype "passive"))
    )
    (net (code "88") (name "Net-(-5V_REG-OUT+)") (class "Default")
      (node (ref "-5V_REG") (pin "11") (pinfunction "OUT+_11") (pintype "power_in"))
      (node (ref "C28") (pin "2") (pinfunction "2_2") (pintype "passive"))
    )
    (net (code "89") (name "Net-(-5V_REG-PGOOD)") (class "Default")
      (node (ref "-5V_REG") (pin "1") (pinfunction "PGOOD_1") (pintype "passive"))
      (node (ref "Rpu1") (pin "2") (pinfunction "2_2") (pintype "passive"))
    )
    (net (code "90") (name "Net-(3.3V_REG-SS)") (class "Default")
      (node (ref "3.3V_REG") (pin "6") (pinfunction "SS_6") (pintype "passive"))
      (node (ref "c5") (pin "2") (pinfunction "2_2") (pintype "passive"))
    )
    (net (code "91") (name "Net-(5V_REG-SS)") (class "Default")
      (node (ref "5V_REG") (pin "6") (pinfunction "SS_6") (pintype "passive"))
      (node (ref "c4") (pin "2") (pinfunction "2_2") (pintype "passive"))
    )
    (net (code "92") (name "unconnected-(-5V_REG-FB+-Pad2)") (class "Default")
      (node (ref "-5V_REG") (pin "2") (pinfunction "FB+_2") (pintype "power_in"))
    )
  )
)
